# BMS.net
KiCad netlist of a schematic drawn in EAGLE
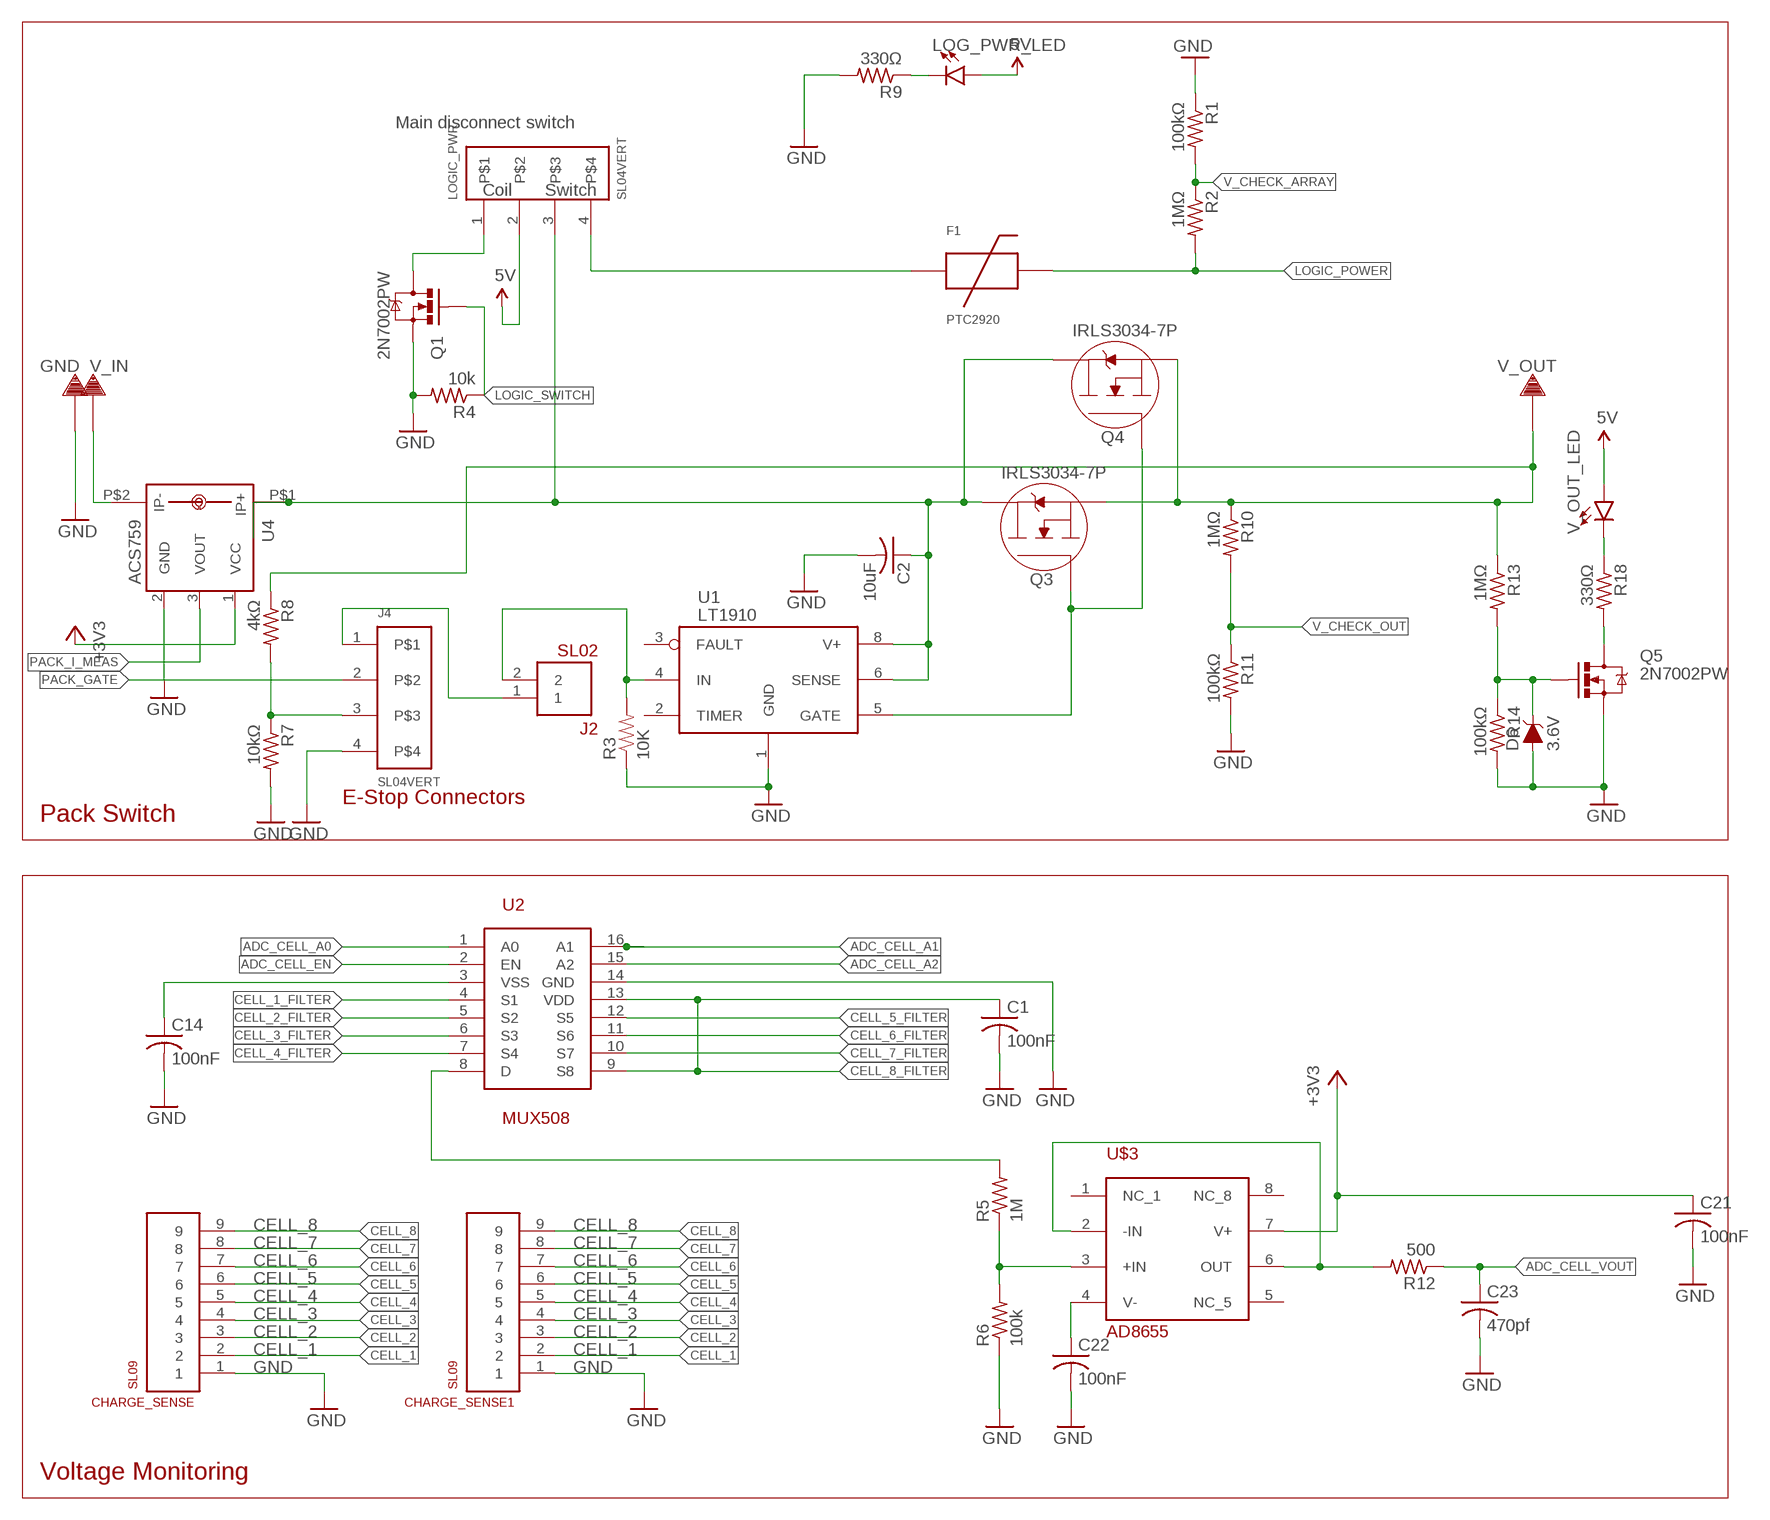
[diagram p0: schematic, sheet 1, part 1 of 2]
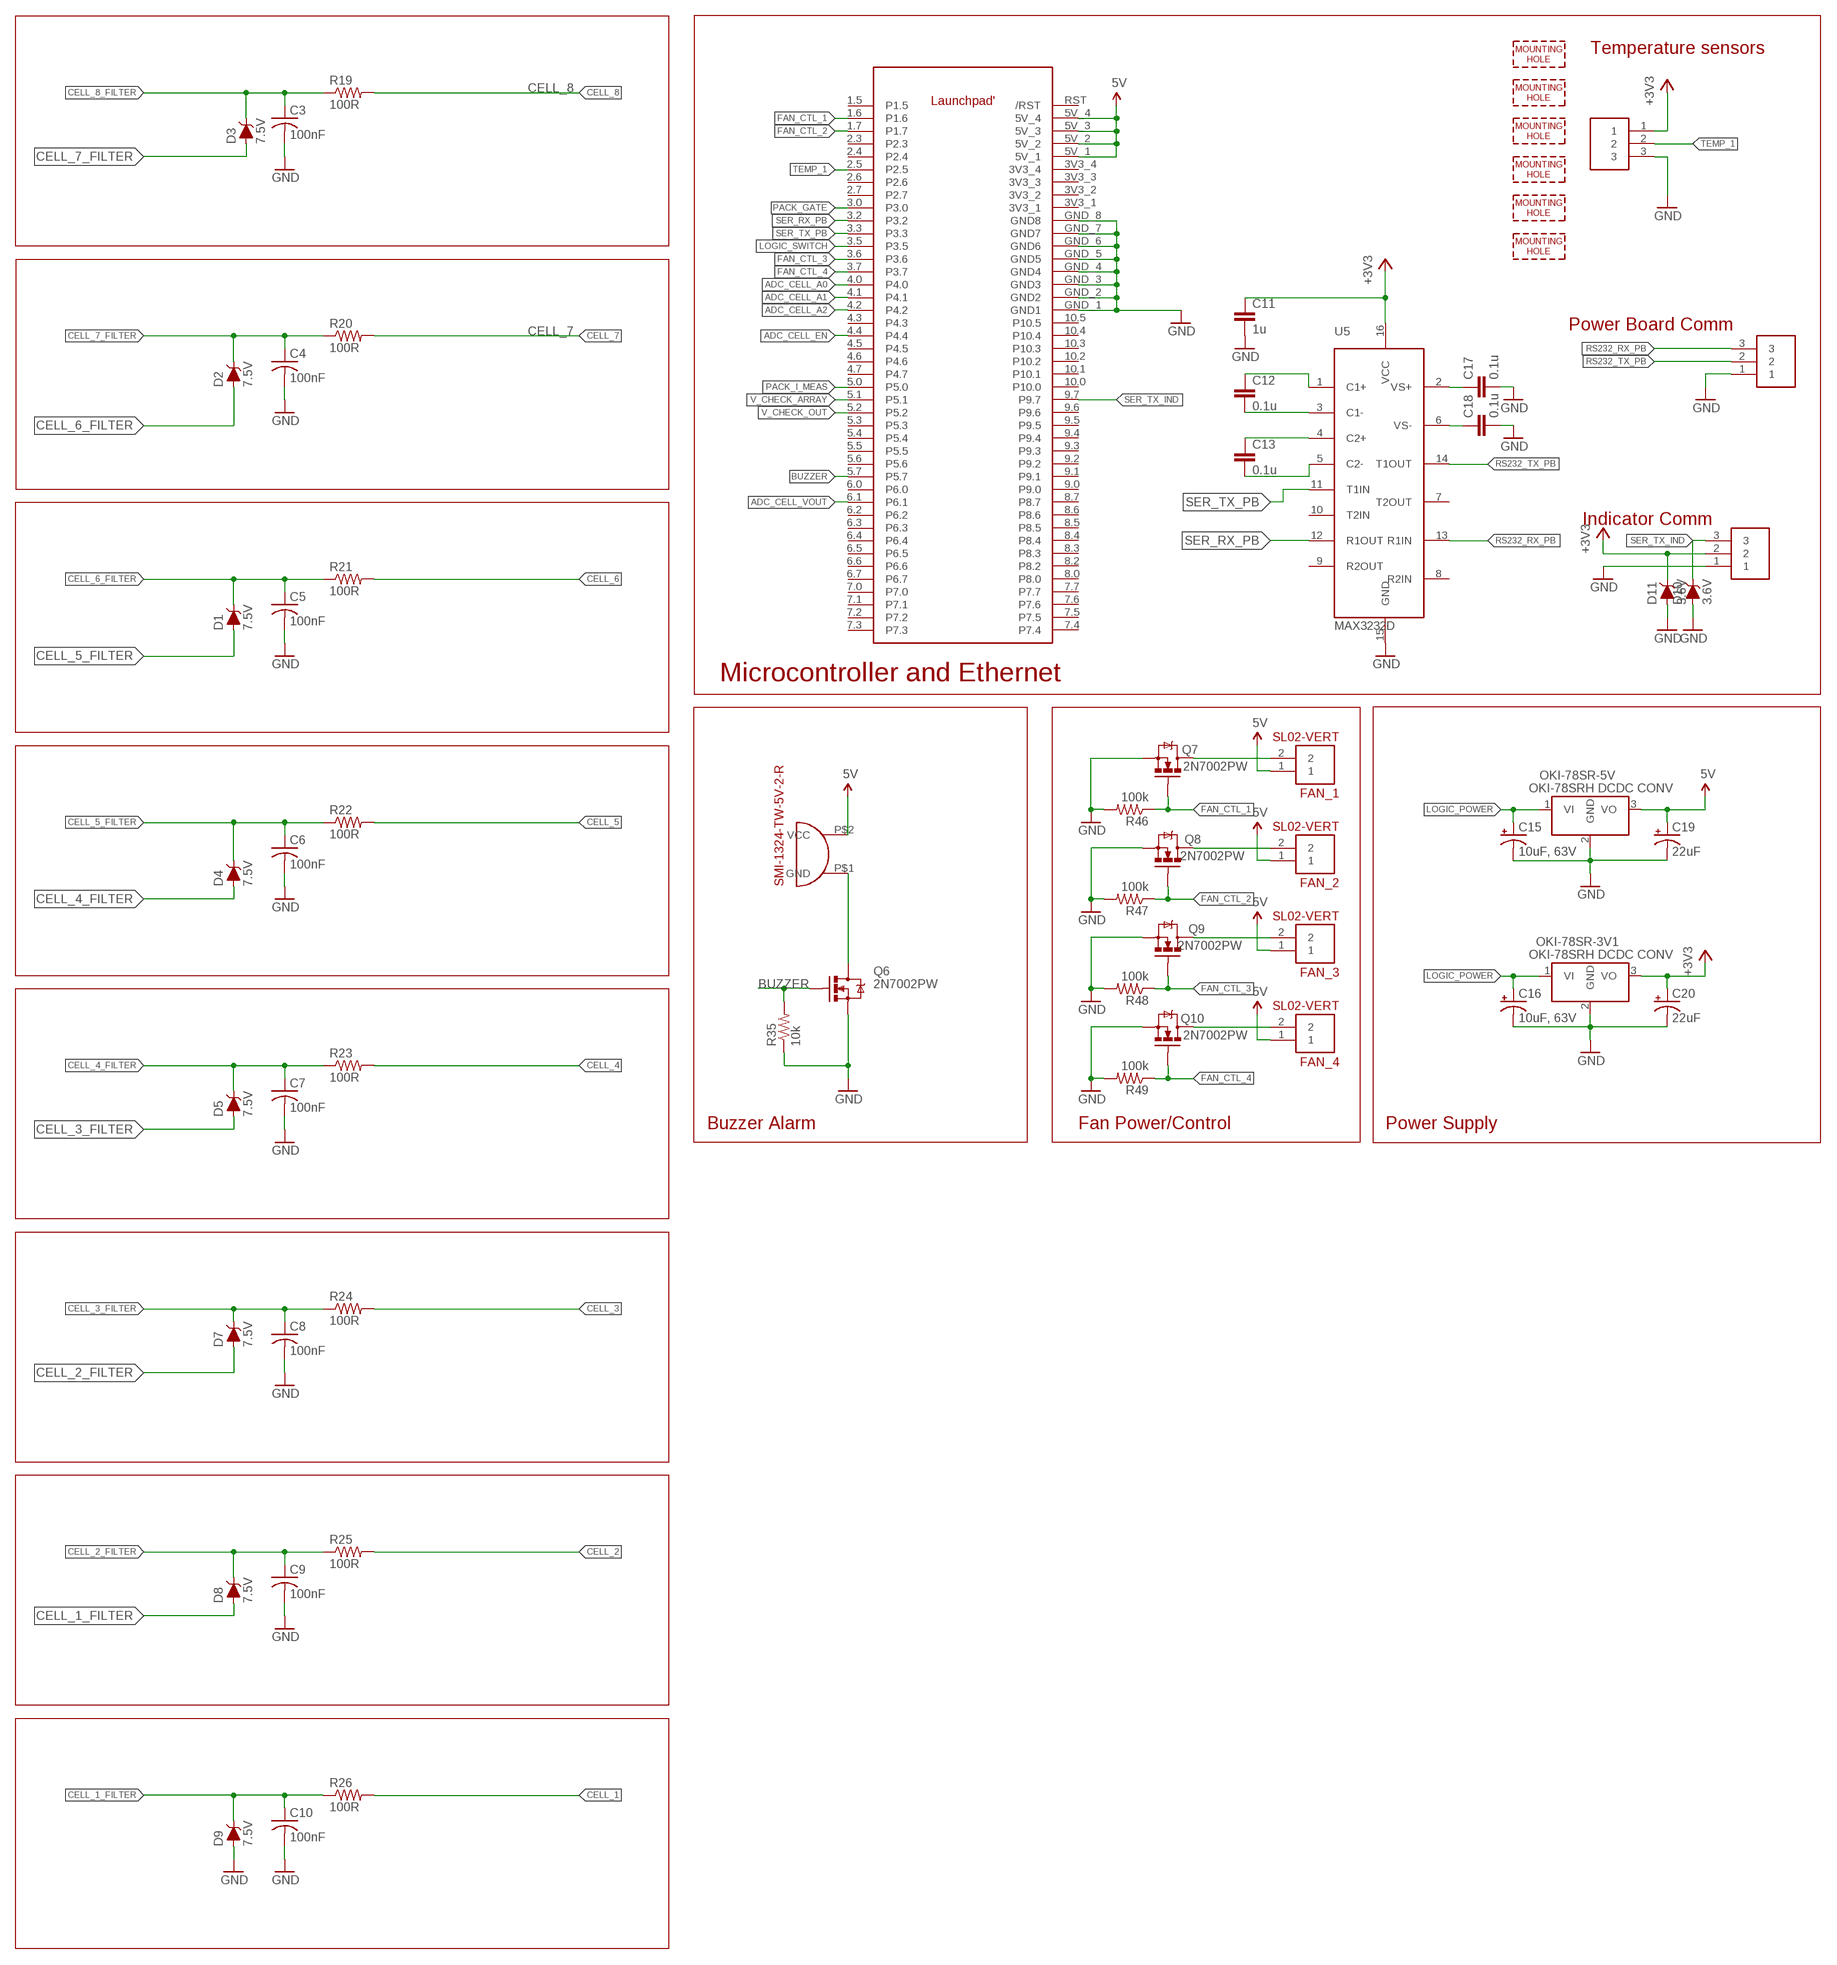
[diagram p1: schematic, sheet 1, part 2 of 2]

(export (version "E")
  (design (tool "Eeschema 10.0.6"))
  (components
    (comp (ref "C1")
      (value "100nF")
      (footprint "eagle-import:C0603")
      (libsource (lib "eagle-import") (part "C-USC0603"))
    )
    (comp (ref "C2")
      (value "10uF")
      (footprint "eagle-import:C0805")
      (libsource (lib "eagle-import") (part "C-USC0805"))
    )
    (comp (ref "C3")
      (value "100nF")
      (footprint "eagle-import:C0603")
      (libsource (lib "eagle-import") (part "C-USC0603"))
    )
    (comp (ref "C4")
      (value "100nF")
      (footprint "eagle-import:C0603")
      (libsource (lib "eagle-import") (part "C-USC0603"))
    )
    (comp (ref "C5")
      (value "100nF")
      (footprint "eagle-import:C0603")
      (libsource (lib "eagle-import") (part "C-USC0603"))
    )
    (comp (ref "C6")
      (value "100nF")
      (footprint "eagle-import:C0603")
      (libsource (lib "eagle-import") (part "C-USC0603"))
    )
    (comp (ref "C7")
      (value "100nF")
      (footprint "eagle-import:C0603")
      (libsource (lib "eagle-import") (part "C-USC0603"))
    )
    (comp (ref "C8")
      (value "100nF")
      (footprint "eagle-import:C0603")
      (libsource (lib "eagle-import") (part "C-USC0603"))
    )
    (comp (ref "C9")
      (value "100nF")
      (footprint "eagle-import:C0603")
      (libsource (lib "eagle-import") (part "C-USC0603"))
    )
    (comp (ref "C10")
      (value "100nF")
      (footprint "eagle-import:C0603")
      (libsource (lib "eagle-import") (part "C-USC0603"))
    )
    (comp (ref "C11")
      (value "1u")
      (footprint "eagle-import:0805")
      (libsource (lib "eagle-import") (part "CAP0805"))
    )
    (comp (ref "C12")
      (value "0.1u")
      (footprint "eagle-import:0805")
      (libsource (lib "eagle-import") (part "CAP0805"))
    )
    (comp (ref "C13")
      (value "0.1u")
      (footprint "eagle-import:0805")
      (libsource (lib "eagle-import") (part "CAP0805"))
    )
    (comp (ref "C14")
      (value "100nF")
      (footprint "eagle-import:C0603")
      (libsource (lib "eagle-import") (part "C-USC0603"))
    )
    (comp (ref "C15")
      (value "10uF, 63V")
      (footprint "eagle-import:PANASONIC_D")
      (libsource (lib "eagle-import") (part "CPOL-USD"))
    )
    (comp (ref "C16")
      (value "10uF, 63V")
      (footprint "eagle-import:PANASONIC_D")
      (libsource (lib "eagle-import") (part "CPOL-USD"))
    )
    (comp (ref "C17")
      (value "0.1u")
      (footprint "eagle-import:0805")
      (libsource (lib "eagle-import") (part "CAP0805"))
    )
    (comp (ref "C18")
      (value "0.1u")
      (footprint "eagle-import:0805")
      (libsource (lib "eagle-import") (part "CAP0805"))
    )
    (comp (ref "C19")
      (value "22uF")
      (footprint "eagle-import:PANASONIC_D")
      (libsource (lib "eagle-import") (part "CPOL-USD"))
    )
    (comp (ref "C20")
      (value "22uF")
      (footprint "eagle-import:PANASONIC_D")
      (libsource (lib "eagle-import") (part "CPOL-USD"))
    )
    (comp (ref "C21")
      (value "100nF")
      (footprint "eagle-import:C0603")
      (libsource (lib "eagle-import") (part "C-USC0603"))
    )
    (comp (ref "C22")
      (value "100nF")
      (footprint "eagle-import:C0603")
      (libsource (lib "eagle-import") (part "C-USC0603"))
    )
    (comp (ref "C23")
      (value "470pf")
      (footprint "eagle-import:C0603")
      (libsource (lib "eagle-import") (part "C-USC0603"))
    )
    (comp (ref "CHARGE_SENSE")
      (value "SL09")
      (footprint "eagle-import:MOLEX-70543-0008")
      (libsource (lib "eagle-import") (part "SL09"))
    )
    (comp (ref "CHARGE_SENSE1")
      (value "SL09")
      (footprint "eagle-import:MOLEX-70543-0008")
      (libsource (lib "eagle-import") (part "SL09"))
    )
    (comp (ref "D1")
      (value "7.5V")
      (footprint "eagle-import:SOD-323")
      (libsource (lib "eagle-import") (part "DIODE-ZENER-BZT52C3V6S"))
    )
    (comp (ref "D2")
      (value "7.5V")
      (footprint "eagle-import:SOD-323")
      (libsource (lib "eagle-import") (part "DIODE-ZENER-BZT52C3V6S"))
    )
    (comp (ref "D3")
      (value "7.5V")
      (footprint "eagle-import:SOD-323")
      (libsource (lib "eagle-import") (part "DIODE-ZENER-BZT52C3V6S"))
    )
    (comp (ref "D4")
      (value "7.5V")
      (footprint "eagle-import:SOD-323")
      (libsource (lib "eagle-import") (part "DIODE-ZENER-BZT52C3V6S"))
    )
    (comp (ref "D5")
      (value "7.5V")
      (footprint "eagle-import:SOD-323")
      (libsource (lib "eagle-import") (part "DIODE-ZENER-BZT52C3V6S"))
    )
    (comp (ref "D6")
      (value "3.6V")
      (footprint "eagle-import:SOD-323")
      (libsource (lib "eagle-import") (part "DIODE-ZENER-BZT52C3V6S"))
    )
    (comp (ref "D7")
      (value "7.5V")
      (footprint "eagle-import:SOD-323")
      (libsource (lib "eagle-import") (part "DIODE-ZENER-BZT52C3V6S"))
    )
    (comp (ref "D8")
      (value "7.5V")
      (footprint "eagle-import:SOD-323")
      (libsource (lib "eagle-import") (part "DIODE-ZENER-BZT52C3V6S"))
    )
    (comp (ref "D9")
      (value "7.5V")
      (footprint "eagle-import:SOD-323")
      (libsource (lib "eagle-import") (part "DIODE-ZENER-BZT52C3V6S"))
    )
    (comp (ref "D10")
      (value "3.6V")
      (footprint "eagle-import:SOD-323")
      (libsource (lib "eagle-import") (part "DIODE-ZENER-BZT52C3V6S"))
    )
    (comp (ref "D11")
      (value "3.6V")
      (footprint "eagle-import:SOD-323")
      (libsource (lib "eagle-import") (part "DIODE-ZENER-BZT52C3V6S"))
    )
    (comp (ref "F1")
      (value "PTC2920")
      (footprint "eagle-import:2920")
      (libsource (lib "eagle-import") (part "PTC2920"))
    )
    (comp (ref "FAN_1")
      (value "SL02-VERT")
      (footprint "eagle-import:MOLEX-70543-0001")
      (libsource (lib "eagle-import") (part "SL02-VERT"))
    )
    (comp (ref "FAN_2")
      (value "SL02-VERT")
      (footprint "eagle-import:MOLEX-70543-0001")
      (libsource (lib "eagle-import") (part "SL02-VERT"))
    )
    (comp (ref "FAN_3")
      (value "SL02-VERT")
      (footprint "eagle-import:MOLEX-70543-0001")
      (libsource (lib "eagle-import") (part "SL02-VERT"))
    )
    (comp (ref "FAN_4")
      (value "SL02-VERT")
      (footprint "eagle-import:MOLEX-70543-0001")
      (libsource (lib "eagle-import") (part "SL02-VERT"))
    )
    (comp (ref "GND")
      (value "TERMINAL_HOLE")
      (footprint "eagle-import:LARGE_TERMINAL_HOLE")
      (libsource (lib "eagle-import") (part "TERMINAL_HOLE"))
    )
    (comp (ref "H1")
      (value "MOUNTING_HOLE#4")
      (footprint "eagle-import:#4_SCREW")
      (libsource (lib "eagle-import") (part "MOUNTING_HOLE#4"))
    )
    (comp (ref "H2")
      (value "MOUNTING_HOLE#4")
      (footprint "eagle-import:#4_SCREW")
      (libsource (lib "eagle-import") (part "MOUNTING_HOLE#4"))
    )
    (comp (ref "H3")
      (value "MOUNTING_HOLE#4")
      (footprint "eagle-import:#4_SCREW")
      (libsource (lib "eagle-import") (part "MOUNTING_HOLE#4"))
    )
    (comp (ref "H4")
      (value "MOUNTING_HOLE#4")
      (footprint "eagle-import:#4_SCREW")
      (libsource (lib "eagle-import") (part "MOUNTING_HOLE#4"))
    )
    (comp (ref "H5")
      (value "MOUNTING_HOLE#4")
      (footprint "eagle-import:#4_SCREW")
      (libsource (lib "eagle-import") (part "MOUNTING_HOLE#4"))
    )
    (comp (ref "H6")
      (value "MOUNTING_HOLE#4")
      (footprint "eagle-import:#4_SCREW")
      (libsource (lib "eagle-import") (part "MOUNTING_HOLE#4"))
    )
    (comp (ref "IC2")
      (value "SMI-1324-TW-5V-2-R")
      (footprint "eagle-import:SMI-1324-TW-5V-2-R")
      (libsource (lib "eagle-import") (part "SMI-1324-TW-5V-2-R"))
    )
    (comp (ref "J1")
      (value "SL03")
      (footprint "eagle-import:MOLEX-70543-0002")
      (libsource (lib "eagle-import") (part "SL03"))
    )
    (comp (ref "J2")
      (value "SL02")
      (footprint "eagle-import:MOLEX-70543-0001")
      (libsource (lib "eagle-import") (part "SL02"))
    )
    (comp (ref "J4")
      (value "SL04VERT")
      (footprint "eagle-import:MOLEX-70543-0003")
      (libsource (lib "eagle-import") (part "SL04VERT"))
    )
    (comp (ref "LOGIC_PWR")
      (value "SL04VERT")
      (footprint "eagle-import:MOLEX-70543-0003")
      (libsource (lib "eagle-import") (part "SL04VERT"))
    )
    (comp (ref "LOG_PWR_LED")
      (value "LED1206")
      (footprint "eagle-import:LED-1206")
      (libsource (lib "eagle-import") (part "LED1206"))
    )
    (comp (ref "OKI-78SR-3V1")
      (value "Q_OKI-78SR12")
      (footprint "eagle-import:OKI-78SRH")
      (libsource (lib "eagle-import") (part "Q_OKI-78SR"))
    )
    (comp (ref "OKI-78SR-5V")
      (value "Q_OKI-78SR5")
      (footprint "eagle-import:OKI-78SRH")
      (libsource (lib "eagle-import") (part "Q_OKI-78SR"))
    )
    (comp (ref "Q1")
      (value "2N7002PW")
      (footprint "eagle-import:SOT323")
      (libsource (lib "eagle-import") (part "MOSFET-NCHANNEL2N7002PW"))
    )
    (comp (ref "Q3")
      (value "IRLS3034-7P")
      (footprint "eagle-import:D2PAK-7")
      (libsource (lib "eagle-import") (part "IRLS3034-7P"))
    )
    (comp (ref "Q4")
      (value "IRLS3034-7P")
      (footprint "eagle-import:D2PAK-7")
      (libsource (lib "eagle-import") (part "IRLS3034-7P"))
    )
    (comp (ref "Q5")
      (value "2N7002PW")
      (footprint "eagle-import:SOT323")
      (libsource (lib "eagle-import") (part "MOSFET-NCHANNEL2N7002PW"))
    )
    (comp (ref "Q6")
      (value "2N7002PW")
      (footprint "eagle-import:SOT323")
      (libsource (lib "eagle-import") (part "MOSFET-NCHANNEL2N7002PW"))
    )
    (comp (ref "Q7")
      (value "2N7002PW")
      (footprint "eagle-import:SOT323")
      (libsource (lib "eagle-import") (part "MOSFET-NCHANNEL2N7002PW"))
    )
    (comp (ref "Q8")
      (value "2N7002PW")
      (footprint "eagle-import:SOT323")
      (libsource (lib "eagle-import") (part "MOSFET-NCHANNEL2N7002PW"))
    )
    (comp (ref "Q9")
      (value "2N7002PW")
      (footprint "eagle-import:SOT323")
      (libsource (lib "eagle-import") (part "MOSFET-NCHANNEL2N7002PW"))
    )
    (comp (ref "Q10")
      (value "2N7002PW")
      (footprint "eagle-import:SOT323")
      (libsource (lib "eagle-import") (part "MOSFET-NCHANNEL2N7002PW"))
    )
    (comp (ref "R1")
      (value "100kΩ")
      (footprint "eagle-import:R0805")
      (libsource (lib "eagle-import") (part "R-US_R0805"))
    )
    (comp (ref "R2")
      (value "1MΩ")
      (footprint "eagle-import:R0805")
      (libsource (lib "eagle-import") (part "R-US_R0805"))
    )
    (comp (ref "R3")
      (value "10K")
      (footprint "eagle-import:0603-RES")
      (libsource (lib "eagle-import") (part "10KOHM-1/10W-1%(0603)0603"))
    )
    (comp (ref "R4")
      (value "10k")
      (footprint "eagle-import:R0805")
      (libsource (lib "eagle-import") (part "R-US_R0805"))
    )
    (comp (ref "R5")
      (value "1M")
      (footprint "eagle-import:M1206")
      (libsource (lib "eagle-import") (part "R-US_M1206"))
    )
    (comp (ref "R6")
      (value "100k")
      (footprint "eagle-import:M1206")
      (libsource (lib "eagle-import") (part "R-US_M1206"))
    )
    (comp (ref "R7")
      (value "10kΩ")
      (footprint "eagle-import:R0805")
      (libsource (lib "eagle-import") (part "R-US_R0805"))
    )
    (comp (ref "R8")
      (value "4kΩ")
      (footprint "eagle-import:R0805")
      (libsource (lib "eagle-import") (part "R-US_R0805"))
    )
    (comp (ref "R9")
      (value "330Ω")
      (footprint "eagle-import:R0805")
      (libsource (lib "eagle-import") (part "R-US_R0805"))
    )
    (comp (ref "R10")
      (value "1MΩ")
      (footprint "eagle-import:R0805")
      (libsource (lib "eagle-import") (part "R-US_R0805"))
    )
    (comp (ref "R11")
      (value "100kΩ")
      (footprint "eagle-import:R0805")
      (libsource (lib "eagle-import") (part "R-US_R0805"))
    )
    (comp (ref "R12")
      (value "500")
      (footprint "eagle-import:M1206")
      (libsource (lib "eagle-import") (part "R-US_M1206"))
    )
    (comp (ref "R13")
      (value "1MΩ")
      (footprint "eagle-import:R0805")
      (libsource (lib "eagle-import") (part "R-US_R0805"))
    )
    (comp (ref "R14")
      (value "100kΩ")
      (footprint "eagle-import:R0805")
      (libsource (lib "eagle-import") (part "R-US_R0805"))
    )
    (comp (ref "R18")
      (value "330Ω")
      (footprint "eagle-import:R0805")
      (libsource (lib "eagle-import") (part "R-US_R0805"))
    )
    (comp (ref "R19")
      (value "100R")
      (footprint "eagle-import:R0603")
      (libsource (lib "eagle-import") (part "R-US_R0603"))
    )
    (comp (ref "R20")
      (value "100R")
      (footprint "eagle-import:R0603")
      (libsource (lib "eagle-import") (part "R-US_R0603"))
    )
    (comp (ref "R21")
      (value "100R")
      (footprint "eagle-import:R0603")
      (libsource (lib "eagle-import") (part "R-US_R0603"))
    )
    (comp (ref "R22")
      (value "100R")
      (footprint "eagle-import:R0603")
      (libsource (lib "eagle-import") (part "R-US_R0603"))
    )
    (comp (ref "R23")
      (value "100R")
      (footprint "eagle-import:R0603")
      (libsource (lib "eagle-import") (part "R-US_R0603"))
    )
    (comp (ref "R24")
      (value "100R")
      (footprint "eagle-import:R0603")
      (libsource (lib "eagle-import") (part "R-US_R0603"))
    )
    (comp (ref "R25")
      (value "100R")
      (footprint "eagle-import:R0603")
      (libsource (lib "eagle-import") (part "R-US_R0603"))
    )
    (comp (ref "R26")
      (value "100R")
      (footprint "eagle-import:R0603")
      (libsource (lib "eagle-import") (part "R-US_R0603"))
    )
    (comp (ref "R35")
      (value "10k")
      (footprint "eagle-import:R0805")
      (libsource (lib "eagle-import") (part "R-US_R0805"))
    )
    (comp (ref "R46")
      (value "100k")
      (footprint "eagle-import:R0805")
      (libsource (lib "eagle-import") (part "R-US_R0805"))
    )
    (comp (ref "R47")
      (value "100k")
      (footprint "eagle-import:R0805")
      (libsource (lib "eagle-import") (part "R-US_R0805"))
    )
    (comp (ref "R48")
      (value "100k")
      (footprint "eagle-import:R0805")
      (libsource (lib "eagle-import") (part "R-US_R0805"))
    )
    (comp (ref "R49")
      (value "100k")
      (footprint "eagle-import:R0805")
      (libsource (lib "eagle-import") (part "R-US_R0805"))
    )
    (comp (ref "RS232_PB")
      (value "SL03")
      (footprint "eagle-import:MOLEX-70543-0002")
      (libsource (lib "eagle-import") (part "SL03"))
    )
    (comp (ref "TEMP_1")
      (value "SL03")
      (footprint "eagle-import:MOLEX-70543-0002")
      (libsource (lib "eagle-import") (part "SL03"))
    )
    (comp (ref "U$3")
      (value "AD8655")
      (footprint "eagle-import:SOIC8")
      (libsource (lib "eagle-import") (part "AD8655"))
    )
    (comp (ref "U1")
      (value "LT1910")
      (footprint "eagle-import:SO8")
      (libsource (lib "eagle-import") (part "LT1910"))
    )
    (comp (ref "U2")
      (value "MUX508")
      (footprint "eagle-import:SOIC16")
      (libsource (lib "eagle-import") (part "MUX508"))
    )
    (comp (ref "U3")
      (value "MSP430R401R")
      (footprint "eagle-import:MSP432R401R-LAUNCHPAD")
      (libsource (lib "eagle-import") (part "MSP430R401R"))
    )
    (comp (ref "U4")
      (value "ACS759")
      (footprint "eagle-import:ACS-PFF-LEADFORM")
      (libsource (lib "eagle-import") (part "ACS759"))
    )
    (comp (ref "U5")
      (value "MAX3232D")
      (footprint "eagle-import:SOIC16")
      (libsource (lib "eagle-import") (part "MAX232D3"))
    )
    (comp (ref "V_IN")
      (value "TERMINAL_HOLE")
      (footprint "eagle-import:LARGE_TERMINAL_HOLE")
      (libsource (lib "eagle-import") (part "TERMINAL_HOLE"))
    )
    (comp (ref "V_OUT")
      (value "TERMINAL_HOLE")
      (footprint "eagle-import:LARGE_TERMINAL_HOLE")
      (libsource (lib "eagle-import") (part "TERMINAL_HOLE"))
    )
    (comp (ref "V_OUT_LED")
      (value "LED1206")
      (footprint "eagle-import:LED-1206")
      (libsource (lib "eagle-import") (part "LED1206"))
    )
  )
  (nets
    (net (code "1") (name "+3V3") (class "Default")
      (node (ref "C11") (pin "1") (pinfunction "1_1") (pintype "passive"))
      (node (ref "C20") (pin "+") (pinfunction "+_+") (pintype "passive"))
      (node (ref "C21") (pin "1") (pinfunction "1_1") (pintype "passive"))
      (node (ref "D11") (pin "C") (pinfunction "C_C") (pintype "passive"))
      (node (ref "J1") (pin "2") (pinfunction "2_2") (pintype "bidirectional"))
      (node (ref "OKI-78SR-3V1") (pin "3") (pinfunction "VO_3") (pintype "bidirectional"))
      (node (ref "TEMP_1") (pin "1") (pinfunction "1_1") (pintype "bidirectional"))
      (node (ref "U$3") (pin "7") (pinfunction "V+_7") (pintype "bidirectional"))
      (node (ref "U4") (pin "1") (pinfunction "VCC_1") (pintype "power_in"))
      (node (ref "U5") (pin "16") (pinfunction "VCC_16") (pintype "bidirectional"))
    )
    (net (code "2") (name "5V") (class "Default")
      (node (ref "C19") (pin "+") (pinfunction "+_+") (pintype "passive"))
      (node (ref "FAN_1") (pin "1") (pinfunction "1_1") (pintype "bidirectional"))
      (node (ref "FAN_2") (pin "1") (pinfunction "1_1") (pintype "bidirectional"))
      (node (ref "FAN_3") (pin "1") (pinfunction "1_1") (pintype "bidirectional"))
      (node (ref "FAN_4") (pin "1") (pinfunction "1_1") (pintype "bidirectional"))
      (node (ref "IC2") (pin "P$2") (pinfunction "VCC_P$2") (pintype "bidirectional"))
      (node (ref "LOGIC_PWR") (pin "2") (pinfunction "P$2_2") (pintype "bidirectional"))
      (node (ref "LOG_PWR_LED") (pin "A") (pinfunction "A_A") (pintype "passive"))
      (node (ref "OKI-78SR-5V") (pin "3") (pinfunction "VO_3") (pintype "bidirectional"))
      (node (ref "U3") (pin "5V_1") (pinfunction "5V_1_5V_1") (pintype "bidirectional"))
      (node (ref "U3") (pin "5V_2") (pinfunction "5V_2_5V_2") (pintype "bidirectional"))
      (node (ref "U3") (pin "5V_3") (pinfunction "5V_3_5V_3") (pintype "bidirectional"))
      (node (ref "U3") (pin "5V_4") (pinfunction "5V_4_5V_4") (pintype "bidirectional"))
      (node (ref "V_OUT_LED") (pin "A") (pinfunction "A_A") (pintype "passive"))
    )
    (net (code "3") (name "ADC_CELL_A0") (class "Default")
      (node (ref "U2") (pin "1") (pinfunction "A0_1") (pintype "bidirectional"))
      (node (ref "U3") (pin "4.0") (pinfunction "P4.0_4.0") (pintype "bidirectional"))
    )
    (net (code "4") (name "ADC_CELL_A1") (class "Default")
      (node (ref "U2") (pin "16") (pinfunction "A1_16") (pintype "bidirectional"))
      (node (ref "U3") (pin "4.1") (pinfunction "P4.1_4.1") (pintype "bidirectional"))
    )
    (net (code "5") (name "ADC_CELL_A2") (class "Default")
      (node (ref "U2") (pin "15") (pinfunction "A2_15") (pintype "bidirectional"))
      (node (ref "U3") (pin "4.2") (pinfunction "P4.2_4.2") (pintype "bidirectional"))
    )
    (net (code "6") (name "ADC_CELL_EN") (class "Default")
      (node (ref "U2") (pin "2") (pinfunction "EN_2") (pintype "bidirectional"))
      (node (ref "U3") (pin "4.4") (pinfunction "P4.4_4.4") (pintype "bidirectional"))
    )
    (net (code "7") (name "ADC_CELL_VOUT") (class "Default")
      (node (ref "C23") (pin "1") (pinfunction "1_1") (pintype "passive"))
      (node (ref "R12") (pin "1") (pinfunction "1_1") (pintype "passive"))
      (node (ref "U3") (pin "6.1") (pinfunction "P6.1_6.1") (pintype "bidirectional"))
    )
    (net (code "8") (name "BUZZER") (class "Default")
      (node (ref "Q6") (pin "1") (pinfunction "G_1") (pintype "passive"))
      (node (ref "R35") (pin "2") (pinfunction "2_2") (pintype "passive"))
      (node (ref "U3") (pin "5.7") (pinfunction "P5.7_5.7") (pintype "bidirectional"))
    )
    (net (code "9") (name "CELL_1") (class "Default")
      (node (ref "CHARGE_SENSE") (pin "2") (pinfunction "2_2") (pintype "bidirectional"))
      (node (ref "CHARGE_SENSE1") (pin "2") (pinfunction "2_2") (pintype "bidirectional"))
      (node (ref "R26") (pin "2") (pinfunction "2_2") (pintype "passive"))
    )
    (net (code "10") (name "CELL_1_FILTER") (class "Default")
      (node (ref "C10") (pin "1") (pinfunction "1_1") (pintype "passive"))
      (node (ref "D8") (pin "A") (pinfunction "A_A") (pintype "passive"))
      (node (ref "D9") (pin "C") (pinfunction "C_C") (pintype "passive"))
      (node (ref "R26") (pin "1") (pinfunction "1_1") (pintype "passive"))
      (node (ref "U2") (pin "4") (pinfunction "S1_4") (pintype "bidirectional"))
    )
    (net (code "11") (name "CELL_2") (class "Default")
      (node (ref "CHARGE_SENSE") (pin "3") (pinfunction "3_3") (pintype "bidirectional"))
      (node (ref "CHARGE_SENSE1") (pin "3") (pinfunction "3_3") (pintype "bidirectional"))
      (node (ref "R25") (pin "2") (pinfunction "2_2") (pintype "passive"))
    )
    (net (code "12") (name "CELL_2_FILTER") (class "Default")
      (node (ref "C9") (pin "1") (pinfunction "1_1") (pintype "passive"))
      (node (ref "D7") (pin "A") (pinfunction "A_A") (pintype "passive"))
      (node (ref "D8") (pin "C") (pinfunction "C_C") (pintype "passive"))
      (node (ref "R25") (pin "1") (pinfunction "1_1") (pintype "passive"))
      (node (ref "U2") (pin "5") (pinfunction "S2_5") (pintype "bidirectional"))
    )
    (net (code "13") (name "CELL_3") (class "Default")
      (node (ref "CHARGE_SENSE") (pin "4") (pinfunction "4_4") (pintype "bidirectional"))
      (node (ref "CHARGE_SENSE1") (pin "4") (pinfunction "4_4") (pintype "bidirectional"))
      (node (ref "R24") (pin "2") (pinfunction "2_2") (pintype "passive"))
    )
    (net (code "14") (name "CELL_3_FILTER") (class "Default")
      (node (ref "C8") (pin "1") (pinfunction "1_1") (pintype "passive"))
      (node (ref "D5") (pin "A") (pinfunction "A_A") (pintype "passive"))
      (node (ref "D7") (pin "C") (pinfunction "C_C") (pintype "passive"))
      (node (ref "R24") (pin "1") (pinfunction "1_1") (pintype "passive"))
      (node (ref "U2") (pin "6") (pinfunction "S3_6") (pintype "bidirectional"))
    )
    (net (code "15") (name "CELL_4") (class "Default")
      (node (ref "CHARGE_SENSE") (pin "5") (pinfunction "5_5") (pintype "bidirectional"))
      (node (ref "CHARGE_SENSE1") (pin "5") (pinfunction "5_5") (pintype "bidirectional"))
      (node (ref "R23") (pin "2") (pinfunction "2_2") (pintype "passive"))
    )
    (net (code "16") (name "CELL_4_FILTER") (class "Default")
      (node (ref "C7") (pin "1") (pinfunction "1_1") (pintype "passive"))
      (node (ref "D4") (pin "A") (pinfunction "A_A") (pintype "passive"))
      (node (ref "D5") (pin "C") (pinfunction "C_C") (pintype "passive"))
      (node (ref "R23") (pin "1") (pinfunction "1_1") (pintype "passive"))
      (node (ref "U2") (pin "7") (pinfunction "S4_7") (pintype "bidirectional"))
    )
    (net (code "17") (name "CELL_5") (class "Default")
      (node (ref "CHARGE_SENSE") (pin "6") (pinfunction "6_6") (pintype "bidirectional"))
      (node (ref "CHARGE_SENSE1") (pin "6") (pinfunction "6_6") (pintype "bidirectional"))
      (node (ref "R22") (pin "2") (pinfunction "2_2") (pintype "passive"))
    )
    (net (code "18") (name "CELL_5_FILTER") (class "Default")
      (node (ref "C6") (pin "1") (pinfunction "1_1") (pintype "passive"))
      (node (ref "D1") (pin "A") (pinfunction "A_A") (pintype "passive"))
      (node (ref "D4") (pin "C") (pinfunction "C_C") (pintype "passive"))
      (node (ref "R22") (pin "1") (pinfunction "1_1") (pintype "passive"))
      (node (ref "U2") (pin "12") (pinfunction "S5_12") (pintype "bidirectional"))
    )
    (net (code "19") (name "CELL_6") (class "Default")
      (node (ref "CHARGE_SENSE") (pin "7") (pinfunction "7_7") (pintype "bidirectional"))
      (node (ref "CHARGE_SENSE1") (pin "7") (pinfunction "7_7") (pintype "bidirectional"))
      (node (ref "R21") (pin "2") (pinfunction "2_2") (pintype "passive"))
    )
    (net (code "20") (name "CELL_6_FILTER") (class "Default")
      (node (ref "C5") (pin "1") (pinfunction "1_1") (pintype "passive"))
      (node (ref "D1") (pin "C") (pinfunction "C_C") (pintype "passive"))
      (node (ref "D2") (pin "A") (pinfunction "A_A") (pintype "passive"))
      (node (ref "R21") (pin "1") (pinfunction "1_1") (pintype "passive"))
      (node (ref "U2") (pin "11") (pinfunction "S6_11") (pintype "bidirectional"))
    )
    (net (code "21") (name "CELL_7") (class "Default")
      (node (ref "CHARGE_SENSE") (pin "8") (pinfunction "8_8") (pintype "bidirectional"))
      (node (ref "CHARGE_SENSE1") (pin "8") (pinfunction "8_8") (pintype "bidirectional"))
      (node (ref "R20") (pin "2") (pinfunction "2_2") (pintype "passive"))
    )
    (net (code "22") (name "CELL_7_FILTER") (class "Default")
      (node (ref "C4") (pin "1") (pinfunction "1_1") (pintype "passive"))
      (node (ref "D2") (pin "C") (pinfunction "C_C") (pintype "passive"))
      (node (ref "D3") (pin "A") (pinfunction "A_A") (pintype "passive"))
      (node (ref "R20") (pin "1") (pinfunction "1_1") (pintype "passive"))
      (node (ref "U2") (pin "10") (pinfunction "S7_10") (pintype "bidirectional"))
    )
    (net (code "23") (name "CELL_8") (class "Default")
      (node (ref "CHARGE_SENSE") (pin "9") (pinfunction "9_9") (pintype "bidirectional"))
      (node (ref "CHARGE_SENSE1") (pin "9") (pinfunction "9_9") (pintype "bidirectional"))
      (node (ref "R19") (pin "2") (pinfunction "2_2") (pintype "passive"))
    )
    (net (code "24") (name "CELL_8_FILTER") (class "Default")
      (node (ref "C1") (pin "1") (pinfunction "1_1") (pintype "passive"))
      (node (ref "C3") (pin "1") (pinfunction "1_1") (pintype "passive"))
      (node (ref "D3") (pin "C") (pinfunction "C_C") (pintype "passive"))
      (node (ref "R19") (pin "1") (pinfunction "1_1") (pintype "passive"))
      (node (ref "U2") (pin "13") (pinfunction "VDD_13") (pintype "bidirectional"))
      (node (ref "U2") (pin "9") (pinfunction "S8_9") (pintype "bidirectional"))
    )
    (net (code "25") (name "FAN_CTL_1") (class "Default")
      (node (ref "Q7") (pin "1") (pinfunction "G_1") (pintype "passive"))
      (node (ref "R46") (pin "1") (pinfunction "1_1") (pintype "passive"))
      (node (ref "U3") (pin "1.6") (pinfunction "P1.6_1.6") (pintype "bidirectional"))
    )
    (net (code "26") (name "FAN_CTL_2") (class "Default")
      (node (ref "Q8") (pin "1") (pinfunction "G_1") (pintype "passive"))
      (node (ref "R47") (pin "1") (pinfunction "1_1") (pintype "passive"))
      (node (ref "U3") (pin "1.7") (pinfunction "P1.7_1.7") (pintype "bidirectional"))
    )
    (net (code "27") (name "FAN_CTL_3") (class "Default")
      (node (ref "Q9") (pin "1") (pinfunction "G_1") (pintype "passive"))
      (node (ref "R48") (pin "1") (pinfunction "1_1") (pintype "passive"))
      (node (ref "U3") (pin "3.6") (pinfunction "P3.6_3.6") (pintype "bidirectional"))
    )
    (net (code "28") (name "FAN_CTL_4") (class "Default")
      (node (ref "Q10") (pin "1") (pinfunction "G_1") (pintype "passive"))
      (node (ref "R49") (pin "1") (pinfunction "1_1") (pintype "passive"))
      (node (ref "U3") (pin "3.7") (pinfunction "P3.7_3.7") (pintype "bidirectional"))
    )
    (net (code "29") (name "GND") (class "Default")
      (node (ref "C1") (pin "2") (pinfunction "2_2") (pintype "passive"))
      (node (ref "C10") (pin "2") (pinfunction "2_2") (pintype "passive"))
      (node (ref "C11") (pin "2") (pinfunction "2_2") (pintype "passive"))
      (node (ref "C14") (pin "2") (pinfunction "2_2") (pintype "passive"))
      (node (ref "C15") (pin "-") (pinfunction "-_-") (pintype "passive"))
      (node (ref "C16") (pin "-") (pinfunction "-_-") (pintype "passive"))
      (node (ref "C17") (pin "2") (pinfunction "2_2") (pintype "passive"))
      (node (ref "C18") (pin "2") (pinfunction "2_2") (pintype "passive"))
      (node (ref "C19") (pin "-") (pinfunction "-_-") (pintype "passive"))
      (node (ref "C2") (pin "2") (pinfunction "2_2") (pintype "passive"))
      (node (ref "C20") (pin "-") (pinfunction "-_-") (pintype "passive"))
      (node (ref "C21") (pin "2") (pinfunction "2_2") (pintype "passive"))
      (node (ref "C22") (pin "2") (pinfunction "2_2") (pintype "passive"))
      (node (ref "C23") (pin "2") (pinfunction "2_2") (pintype "passive"))
      (node (ref "C3") (pin "2") (pinfunction "2_2") (pintype "passive"))
      (node (ref "C4") (pin "2") (pinfunction "2_2") (pintype "passive"))
      (node (ref "C5") (pin "2") (pinfunction "2_2") (pintype "passive"))
      (node (ref "C6") (pin "2") (pinfunction "2_2") (pintype "passive"))
      (node (ref "C7") (pin "2") (pinfunction "2_2") (pintype "passive"))
      (node (ref "C8") (pin "2") (pinfunction "2_2") (pintype "passive"))
      (node (ref "C9") (pin "2") (pinfunction "2_2") (pintype "passive"))
      (node (ref "CHARGE_SENSE") (pin "1") (pinfunction "1_1") (pintype "bidirectional"))
      (node (ref "CHARGE_SENSE1") (pin "1") (pinfunction "1_1") (pintype "bidirectional"))
      (node (ref "D10") (pin "A") (pinfunction "A_A") (pintype "passive"))
      (node (ref "D11") (pin "A") (pinfunction "A_A") (pintype "passive"))
      (node (ref "D6") (pin "A") (pinfunction "A_A") (pintype "passive"))
      (node (ref "D9") (pin "A") (pinfunction "A_A") (pintype "passive"))
      (node (ref "GND") (pin "P$1") (pinfunction "P$1_P$1") (pintype "bidirectional"))
      (node (ref "J1") (pin "1") (pinfunction "1_1") (pintype "bidirectional"))
      (node (ref "J4") (pin "4") (pinfunction "P$4_4") (pintype "bidirectional"))
      (node (ref "OKI-78SR-3V1") (pin "2") (pinfunction "GND_2") (pintype "bidirectional"))
      (node (ref "OKI-78SR-5V") (pin "2") (pinfunction "GND_2") (pintype "bidirectional"))
      (node (ref "Q1") (pin "2") (pinfunction "S_2") (pintype "passive"))
      (node (ref "Q10") (pin "2") (pinfunction "S_2") (pintype "passive"))
      (node (ref "Q5") (pin "2") (pinfunction "S_2") (pintype "passive"))
      (node (ref "Q6") (pin "2") (pinfunction "S_2") (pintype "passive"))
      (node (ref "Q7") (pin "2") (pinfunction "S_2") (pintype "passive"))
      (node (ref "Q8") (pin "2") (pinfunction "S_2") (pintype "passive"))
      (node (ref "Q9") (pin "2") (pinfunction "S_2") (pintype "passive"))
      (node (ref "R1") (pin "1") (pinfunction "1_1") (pintype "passive"))
      (node (ref "R11") (pin "2") (pinfunction "2_2") (pintype "passive"))
      (node (ref "R14") (pin "2") (pinfunction "2_2") (pintype "passive"))
      (node (ref "R3") (pin "1") (pinfunction "1_1") (pintype "passive"))
      (node (ref "R35") (pin "1") (pinfunction "1_1") (pintype "passive"))
      (node (ref "R4") (pin "2") (pinfunction "2_2") (pintype "passive"))
      (node (ref "R46") (pin "2") (pinfunction "2_2") (pintype "passive"))
      (node (ref "R47") (pin "2") (pinfunction "2_2") (pintype "passive"))
      (node (ref "R48") (pin "2") (pinfunction "2_2") (pintype "passive"))
      (node (ref "R49") (pin "2") (pinfunction "2_2") (pintype "passive"))
      (node (ref "R6") (pin "1") (pinfunction "1_1") (pintype "passive"))
      (node (ref "R7") (pin "2") (pinfunction "2_2") (pintype "passive"))
      (node (ref "R9") (pin "2") (pinfunction "2_2") (pintype "passive"))
      (node (ref "RS232_PB") (pin "1") (pinfunction "1_1") (pintype "bidirectional"))
      (node (ref "TEMP_1") (pin "3") (pinfunction "3_3") (pintype "bidirectional"))
      (node (ref "U1") (pin "1") (pinfunction "GND_1") (pintype "bidirectional"))
      (node (ref "U2") (pin "14") (pinfunction "GND_14") (pintype "bidirectional"))
      (node (ref "U3") (pin "GND_1") (pinfunction "GND1_GND_1") (pintype "bidirectional"))
      (node (ref "U3") (pin "GND_2") (pinfunction "GND2_GND_2") (pintype "bidirectional"))
      (node (ref "U3") (pin "GND_3") (pinfunction "GND3_GND_3") (pintype "bidirectional"))
      (node (ref "U3") (pin "GND_4") (pinfunction "GND4_GND_4") (pintype "bidirectional"))
      (node (ref "U3") (pin "GND_5") (pinfunction "GND5_GND_5") (pintype "bidirectional"))
      (node (ref "U3") (pin "GND_6") (pinfunction "GND6_GND_6") (pintype "bidirectional"))
      (node (ref "U3") (pin "GND_7") (pinfunction "GND7_GND_7") (pintype "bidirectional"))
      (node (ref "U3") (pin "GND_8") (pinfunction "GND8_GND_8") (pintype "bidirectional"))
      (node (ref "U4") (pin "2") (pinfunction "GND_2") (pintype "power_in"))
      (node (ref "U5") (pin "15") (pinfunction "GND_15") (pintype "bidirectional"))
    )
    (net (code "30") (name "LOGIC_POWER") (class "Default")
      (node (ref "C15") (pin "+") (pinfunction "+_+") (pintype "passive"))
      (node (ref "C16") (pin "+") (pinfunction "+_+") (pintype "passive"))
      (node (ref "F1") (pin "P$2") (pinfunction "P$2_P$2") (pintype "bidirectional"))
      (node (ref "OKI-78SR-3V1") (pin "1") (pinfunction "VI_1") (pintype "bidirectional"))
      (node (ref "OKI-78SR-5V") (pin "1") (pinfunction "VI_1") (pintype "bidirectional"))
      (node (ref "R2") (pin "2") (pinfunction "2_2") (pintype "passive"))
    )
    (net (code "31") (name "LOGIC_SWITCH") (class "Default")
      (node (ref "Q1") (pin "1") (pinfunction "G_1") (pintype "passive"))
      (node (ref "R4") (pin "1") (pinfunction "1_1") (pintype "passive"))
      (node (ref "U3") (pin "3.5") (pinfunction "P3.5_3.5") (pintype "bidirectional"))
    )
    (net (code "32") (name "Net-(IC2-GND)") (class "Default")
      (node (ref "IC2") (pin "P$1") (pinfunction "GND_P$1") (pintype "bidirectional"))
      (node (ref "Q6") (pin "3") (pinfunction "D_3") (pintype "passive"))
    )
    (net (code "33") (name "Net-(J4-P$1)") (class "Default")
      (node (ref "J2") (pin "1") (pinfunction "1_1") (pintype "bidirectional"))
      (node (ref "J4") (pin "1") (pinfunction "P$1_1") (pintype "bidirectional"))
    )
    (net (code "34") (name "Net-(J4-P$3)") (class "Default")
      (node (ref "J4") (pin "3") (pinfunction "P$3_3") (pintype "bidirectional"))
      (node (ref "R7") (pin "1") (pinfunction "1_1") (pintype "passive"))
      (node (ref "R8") (pin "2") (pinfunction "2_2") (pintype "passive"))
    )
    (net (code "35") (name "Net-(LOGIC_PWR-P$1)") (class "Default")
      (node (ref "LOGIC_PWR") (pin "1") (pinfunction "P$1_1") (pintype "bidirectional"))
      (node (ref "Q1") (pin "3") (pinfunction "D_3") (pintype "passive"))
    )
    (net (code "36") (name "Net-(LOGIC_PWR-P$3)") (class "Default")
      (node (ref "C2") (pin "1") (pinfunction "1_1") (pintype "passive"))
      (node (ref "LOGIC_PWR") (pin "3") (pinfunction "P$3_3") (pintype "bidirectional"))
      (node (ref "Q3") (pin "PAD") (pinfunction "DRAIN_PAD") (pintype "bidirectional"))
      (node (ref "Q4") (pin "PAD") (pinfunction "DRAIN_PAD") (pintype "bidirectional"))
      (node (ref "U1") (pin "6") (pinfunction "SENSE_6") (pintype "bidirectional"))
      (node (ref "U1") (pin "8") (pinfunction "V+_8") (pintype "bidirectional"))
      (node (ref "U4") (pin "P$1") (pinfunction "IP+_P$1") (pintype "passive"))
    )
    (net (code "37") (name "Net-(LOGIC_PWR-P$4)") (class "Default")
      (node (ref "F1") (pin "P$1") (pinfunction "P$1_P$1") (pintype "bidirectional"))
      (node (ref "LOGIC_PWR") (pin "4") (pinfunction "P$4_4") (pintype "bidirectional"))
    )
    (net (code "38") (name "Net-(LOG_PWR_LED-PadC)") (class "Default")
      (node (ref "LOG_PWR_LED") (pin "C") (pinfunction "C_C") (pintype "passive"))
      (node (ref "R9") (pin "1") (pinfunction "1_1") (pintype "passive"))
    )
    (net (code "39") (name "Net-(Q3-GATE)") (class "Default")
      (node (ref "Q3") (pin "1") (pinfunction "GATE_1") (pintype "bidirectional"))
      (node (ref "Q4") (pin "1") (pinfunction "GATE_1") (pintype "bidirectional"))
      (node (ref "U1") (pin "5") (pinfunction "GATE_5") (pintype "bidirectional"))
    )
    (net (code "40") (name "Net-(Q3-SOURCE-Pad2)") (class "Default")
      (node (ref "Q3") (pin "2") (pinfunction "SOURCE_2") (pintype "bidirectional"))
      (node (ref "Q3") (pin "3") (pinfunction "SOURCE_3") (pintype "bidirectional"))
      (node (ref "Q3") (pin "4") (pinfunction "SOURCE_4") (pintype "bidirectional"))
      (node (ref "Q3") (pin "5") (pinfunction "SOURCE_5") (pintype "bidirectional"))
      (node (ref "Q3") (pin "6") (pinfunction "SOURCE_6") (pintype "bidirectional"))
      (node (ref "Q4") (pin "2") (pinfunction "SOURCE_2") (pintype "bidirectional"))
      (node (ref "Q4") (pin "3") (pinfunction "SOURCE_3") (pintype "bidirectional"))
      (node (ref "Q4") (pin "4") (pinfunction "SOURCE_4") (pintype "bidirectional"))
      (node (ref "Q4") (pin "5") (pinfunction "SOURCE_5") (pintype "bidirectional"))
      (node (ref "Q4") (pin "6") (pinfunction "SOURCE_6") (pintype "bidirectional"))
      (node (ref "R10") (pin "1") (pinfunction "1_1") (pintype "passive"))
      (node (ref "R13") (pin "1") (pinfunction "1_1") (pintype "passive"))
      (node (ref "R8") (pin "1") (pinfunction "1_1") (pintype "passive"))
      (node (ref "V_OUT") (pin "P$1") (pinfunction "P$1_P$1") (pintype "bidirectional"))
    )
    (net (code "41") (name "Net-(Q5-D)") (class "Default")
      (node (ref "Q5") (pin "3") (pinfunction "D_3") (pintype "passive"))
      (node (ref "R18") (pin "2") (pinfunction "2_2") (pintype "passive"))
    )
    (net (code "42") (name "Net-(Q5-G)") (class "Default")
      (node (ref "D6") (pin "C") (pinfunction "C_C") (pintype "passive"))
      (node (ref "Q5") (pin "1") (pinfunction "G_1") (pintype "passive"))
      (node (ref "R13") (pin "2") (pinfunction "2_2") (pintype "passive"))
      (node (ref "R14") (pin "1") (pinfunction "1_1") (pintype "passive"))
    )
    (net (code "43") (name "Net-(Q7-D)") (class "Default")
      (node (ref "FAN_1") (pin "2") (pinfunction "2_2") (pintype "bidirectional"))
      (node (ref "Q7") (pin "3") (pinfunction "D_3") (pintype "passive"))
    )
    (net (code "44") (name "Net-(Q8-D)") (class "Default")
      (node (ref "FAN_2") (pin "2") (pinfunction "2_2") (pintype "bidirectional"))
      (node (ref "Q8") (pin "3") (pinfunction "D_3") (pintype "passive"))
    )
    (net (code "45") (name "Net-(Q9-D)") (class "Default")
      (node (ref "FAN_3") (pin "2") (pinfunction "2_2") (pintype "bidirectional"))
      (node (ref "Q9") (pin "3") (pinfunction "D_3") (pintype "passive"))
    )
    (net (code "46") (name "Net-(Q10-D)") (class "Default")
      (node (ref "FAN_4") (pin "2") (pinfunction "2_2") (pintype "bidirectional"))
      (node (ref "Q10") (pin "3") (pinfunction "D_3") (pintype "passive"))
    )
    (net (code "47") (name "Net-(R18-Pad1)") (class "Default")
      (node (ref "R18") (pin "1") (pinfunction "1_1") (pintype "passive"))
      (node (ref "V_OUT_LED") (pin "C") (pinfunction "C_C") (pintype "passive"))
    )
    (net (code "48") (name "Net-(U$3-+IN)") (class "Default")
      (node (ref "R5") (pin "1") (pinfunction "1_1") (pintype "passive"))
      (node (ref "R6") (pin "2") (pinfunction "2_2") (pintype "passive"))
      (node (ref "U$3") (pin "3") (pinfunction "+IN_3") (pintype "bidirectional"))
    )
    (net (code "49") (name "Net-(U$3--IN)") (class "Default")
      (node (ref "R12") (pin "2") (pinfunction "2_2") (pintype "passive"))
      (node (ref "U$3") (pin "2") (pinfunction "-IN_2") (pintype "bidirectional"))
      (node (ref "U$3") (pin "6") (pinfunction "OUT_6") (pintype "bidirectional"))
    )
    (net (code "50") (name "Net-(U$3-V-)") (class "Default")
      (node (ref "C22") (pin "1") (pinfunction "1_1") (pintype "passive"))
      (node (ref "U$3") (pin "4") (pinfunction "V-_4") (pintype "bidirectional"))
    )
    (net (code "51") (name "Net-(U1-IN)") (class "Default")
      (node (ref "J2") (pin "2") (pinfunction "2_2") (pintype "bidirectional"))
      (node (ref "R3") (pin "2") (pinfunction "2_2") (pintype "passive"))
      (node (ref "U1") (pin "4") (pinfunction "IN_4") (pintype "bidirectional"))
    )
    (net (code "52") (name "Net-(U2-D)") (class "Default")
      (node (ref "R5") (pin "2") (pinfunction "2_2") (pintype "passive"))
      (node (ref "U2") (pin "8") (pinfunction "D_8") (pintype "bidirectional"))
    )
    (net (code "53") (name "Net-(U2-VSS)") (class "Default")
      (node (ref "C14") (pin "1") (pinfunction "1_1") (pintype "passive"))
      (node (ref "U2") (pin "3") (pinfunction "VSS_3") (pintype "bidirectional"))
    )
    (net (code "54") (name "Net-(U4-IP-)") (class "Default")
      (node (ref "U4") (pin "P$2") (pinfunction "IP-_P$2") (pintype "passive"))
      (node (ref "V_IN") (pin "P$1") (pinfunction "P$1_P$1") (pintype "bidirectional"))
    )
    (net (code "55") (name "Net-(U5-C1+)") (class "Default")
      (node (ref "C12") (pin "1") (pinfunction "1_1") (pintype "passive"))
      (node (ref "U5") (pin "1") (pinfunction "C1+_1") (pintype "bidirectional"))
    )
    (net (code "56") (name "Net-(U5-C1-)") (class "Default")
      (node (ref "C12") (pin "2") (pinfunction "2_2") (pintype "passive"))
      (node (ref "U5") (pin "3") (pinfunction "C1-_3") (pintype "bidirectional"))
    )
    (net (code "57") (name "Net-(U5-C2+)") (class "Default")
      (node (ref "C13") (pin "1") (pinfunction "1_1") (pintype "passive"))
      (node (ref "U5") (pin "4") (pinfunction "C2+_4") (pintype "bidirectional"))
    )
    (net (code "58") (name "Net-(U5-C2-)") (class "Default")
      (node (ref "C13") (pin "2") (pinfunction "2_2") (pintype "passive"))
      (node (ref "U5") (pin "5") (pinfunction "C2-_5") (pintype "bidirectional"))
    )
    (net (code "59") (name "Net-(U5-VS+)") (class "Default")
      (node (ref "C17") (pin "1") (pinfunction "1_1") (pintype "passive"))
      (node (ref "U5") (pin "2") (pinfunction "VS+_2") (pintype "bidirectional"))
    )
    (net (code "60") (name "Net-(U5-VS-)") (class "Default")
      (node (ref "C18") (pin "1") (pinfunction "1_1") (pintype "passive"))
      (node (ref "U5") (pin "6") (pinfunction "VS-_6") (pintype "bidirectional"))
    )
    (net (code "61") (name "PACK_GATE") (class "Default")
      (node (ref "J4") (pin "2") (pinfunction "P$2_2") (pintype "bidirectional"))
      (node (ref "U3") (pin "3.0") (pinfunction "P3.0_3.0") (pintype "bidirectional"))
    )
    (net (code "62") (name "PACK_I_MEAS") (class "Default")
      (node (ref "U3") (pin "5.0") (pinfunction "P5.0_5.0") (pintype "bidirectional"))
      (node (ref "U4") (pin "3") (pinfunction "VOUT_3") (pintype "output"))
    )
    (net (code "63") (name "RS232_RX_PB") (class "Default")
      (node (ref "RS232_PB") (pin "3") (pinfunction "3_3") (pintype "bidirectional"))
      (node (ref "U5") (pin "13") (pinfunction "R1IN_13") (pintype "bidirectional"))
    )
    (net (code "64") (name "RS232_TX_PB") (class "Default")
      (node (ref "RS232_PB") (pin "2") (pinfunction "2_2") (pintype "bidirectional"))
      (node (ref "U5") (pin "14") (pinfunction "T1OUT_14") (pintype "bidirectional"))
    )
    (net (code "65") (name "SER_RX_PB") (class "Default")
      (node (ref "U3") (pin "3.2") (pinfunction "P3.2_3.2") (pintype "bidirectional"))
      (node (ref "U5") (pin "12") (pinfunction "R1OUT_12") (pintype "bidirectional"))
    )
    (net (code "66") (name "SER_TX_IND") (class "Default")
      (node (ref "D10") (pin "C") (pinfunction "C_C") (pintype "passive"))
      (node (ref "J1") (pin "3") (pinfunction "3_3") (pintype "bidirectional"))
      (node (ref "U3") (pin "9.7") (pinfunction "P9.7_9.7") (pintype "bidirectional"))
    )
    (net (code "67") (name "SER_TX_PB") (class "Default")
      (node (ref "U3") (pin "3.3") (pinfunction "P3.3_3.3") (pintype "bidirectional"))
      (node (ref "U5") (pin "11") (pinfunction "T1IN_11") (pintype "bidirectional"))
    )
    (net (code "68") (name "TEMP_1") (class "Default")
      (node (ref "TEMP_1") (pin "2") (pinfunction "2_2") (pintype "bidirectional"))
      (node (ref "U3") (pin "2.5") (pinfunction "P2.5_2.5") (pintype "bidirectional"))
    )
    (net (code "69") (name "V_CHECK_ARRAY") (class "Default")
      (node (ref "R1") (pin "2") (pinfunction "2_2") (pintype "passive"))
      (node (ref "R2") (pin "1") (pinfunction "1_1") (pintype "passive"))
      (node (ref "U3") (pin "5.1") (pinfunction "P5.1_5.1") (pintype "bidirectional"))
    )
    (net (code "70") (name "V_CHECK_OUT") (class "Default")
      (node (ref "R10") (pin "2") (pinfunction "2_2") (pintype "passive"))
      (node (ref "R11") (pin "1") (pinfunction "1_1") (pintype "passive"))
      (node (ref "U3") (pin "5.2") (pinfunction "P5.2_5.2") (pintype "bidirectional"))
    )
    (net (code "71") (name "unconnected-(U$3-NC_1-Pad1)") (class "Default")
      (node (ref "U$3") (pin "1") (pinfunction "NC_1_1") (pintype "bidirectional"))
    )
    (net (code "72") (name "unconnected-(U$3-NC_5-Pad5)") (class "Default")
      (node (ref "U$3") (pin "5") (pinfunction "NC_5_5") (pintype "bidirectional"))
    )
    (net (code "73") (name "unconnected-(U$3-NC_8-Pad8)") (class "Default")
      (node (ref "U$3") (pin "8") (pinfunction "NC_8_8") (pintype "bidirectional"))
    )
    (net (code "74") (name "unconnected-(U1-FAULT-Pad3)") (class "Default")
      (node (ref "U1") (pin "3") (pinfunction "FAULT_3") (pintype "bidirectional"))
    )
    (net (code "75") (name "unconnected-(U1-TIMER-Pad2)") (class "Default")
      (node (ref "U1") (pin "2") (pinfunction "TIMER_2") (pintype "bidirectional"))
    )
    (net (code "76") (name "unconnected-(U3-P1.5-Pad1.5)") (class "Default")
      (node (ref "U3") (pin "1.5") (pinfunction "P1.5_1.5") (pintype "bidirectional"))
    )
    (net (code "77") (name "unconnected-(U3-P2.3-Pad2.3)") (class "Default")
      (node (ref "U3") (pin "2.3") (pinfunction "P2.3_2.3") (pintype "bidirectional"))
    )
    (net (code "78") (name "unconnected-(U3-P2.4-Pad2.4)") (class "Default")
      (node (ref "U3") (pin "2.4") (pinfunction "P2.4_2.4") (pintype "bidirectional"))
    )
    (net (code "79") (name "unconnected-(U3-P2.6-Pad2.6)") (class "Default")
      (node (ref "U3") (pin "2.6") (pinfunction "P2.6_2.6") (pintype "bidirectional"))
    )
    (net (code "80") (name "unconnected-(U3-P2.7-Pad2.7)") (class "Default")
      (node (ref "U3") (pin "2.7") (pinfunction "P2.7_2.7") (pintype "bidirectional"))
    )
    (net (code "81") (name "unconnected-(U3-P4.3-Pad4.3)") (class "Default")
      (node (ref "U3") (pin "4.3") (pinfunction "P4.3_4.3") (pintype "bidirectional"))
    )
    (net (code "82") (name "unconnected-(U3-P4.5-Pad4.5)") (class "Default")
      (node (ref "U3") (pin "4.5") (pinfunction "P4.5_4.5") (pintype "bidirectional"))
    )
    (net (code "83") (name "unconnected-(U3-P4.6-Pad4.6)") (class "Default")
      (node (ref "U3") (pin "4.6") (pinfunction "P4.6_4.6") (pintype "bidirectional"))
    )
    (net (code "84") (name "unconnected-(U3-P4.7-Pad4.7)") (class "Default")
      (node (ref "U3") (pin "4.7") (pinfunction "P4.7_4.7") (pintype "bidirectional"))
    )
    (net (code "85") (name "unconnected-(U3-P5.3-Pad5.3)") (class "Default")
      (node (ref "U3") (pin "5.3") (pinfunction "P5.3_5.3") (pintype "bidirectional"))
    )
    (net (code "86") (name "unconnected-(U3-P5.4-Pad5.4)") (class "Default")
      (node (ref "U3") (pin "5.4") (pinfunction "P5.4_5.4") (pintype "bidirectional"))
    )
    (net (code "87") (name "unconnected-(U3-P5.5-Pad5.5)") (class "Default")
      (node (ref "U3") (pin "5.5") (pinfunction "P5.5_5.5") (pintype "bidirectional"))
    )
    (net (code "88") (name "unconnected-(U3-P5.6-Pad5.6)") (class "Default")
      (node (ref "U3") (pin "5.6") (pinfunction "P5.6_5.6") (pintype "bidirectional"))
    )
    (net (code "89") (name "unconnected-(U3-P6.0-Pad6.0)") (class "Default")
      (node (ref "U3") (pin "6.0") (pinfunction "P6.0_6.0") (pintype "bidirectional"))
    )
    (net (code "90") (name "unconnected-(U3-P6.2-Pad6.2)") (class "Default")
      (node (ref "U3") (pin "6.2") (pinfunction "P6.2_6.2") (pintype "bidirectional"))
    )
    (net (code "91") (name "unconnected-(U3-P6.3-Pad6.3)") (class "Default")
      (node (ref "U3") (pin "6.3") (pinfunction "P6.3_6.3") (pintype "bidirectional"))
    )
    (net (code "92") (name "unconnected-(U3-P6.4-Pad6.4)") (class "Default")
      (node (ref "U3") (pin "6.4") (pinfunction "P6.4_6.4") (pintype "bidirectional"))
    )
    (net (code "93") (name "unconnected-(U3-P6.5-Pad6.5)") (class "Default")
      (node (ref "U3") (pin "6.5") (pinfunction "P6.5_6.5") (pintype "bidirectional"))
    )
    (net (code "94") (name "unconnected-(U3-P6.6-Pad6.6)") (class "Default")
      (node (ref "U3") (pin "6.6") (pinfunction "P6.6_6.6") (pintype "bidirectional"))
    )
    (net (code "95") (name "unconnected-(U3-P6.7-Pad6.7)") (class "Default")
      (node (ref "U3") (pin "6.7") (pinfunction "P6.7_6.7") (pintype "bidirectional"))
    )
    (net (code "96") (name "unconnected-(U3-P7.0-Pad7.0)") (class "Default")
      (node (ref "U3") (pin "7.0") (pinfunction "P7.0_7.0") (pintype "bidirectional"))
    )
    (net (code "97") (name "unconnected-(U3-P7.1-Pad7.1)") (class "Default")
      (node (ref "U3") (pin "7.1") (pinfunction "P7.1_7.1") (pintype "bidirectional"))
    )
    (net (code "98") (name "unconnected-(U3-P7.2-Pad7.2)") (class "Default")
      (node (ref "U3") (pin "7.2") (pinfunction "P7.2_7.2") (pintype "bidirectional"))
    )
    (net (code "99") (name "unconnected-(U3-P7.3-Pad7.3)") (class "Default")
      (node (ref "U3") (pin "7.3") (pinfunction "P7.3_7.3") (pintype "bidirectional"))
    )
    (net (code "100") (name "unconnected-(U3-P7.4-Pad7.4)") (class "Default")
      (node (ref "U3") (pin "7.4") (pinfunction "P7.4_7.4") (pintype "bidirectional"))
    )
    (net (code "101") (name "unconnected-(U3-P7.5-Pad7.5)") (class "Default")
      (node (ref "U3") (pin "7.5") (pinfunction "P7.5_7.5") (pintype "bidirectional"))
    )
    (net (code "102") (name "unconnected-(U3-P7.6-Pad7.6)") (class "Default")
      (node (ref "U3") (pin "7.6") (pinfunction "P7.6_7.6") (pintype "bidirectional"))
    )
    (net (code "103") (name "unconnected-(U3-P7.7-Pad7.7)") (class "Default")
      (node (ref "U3") (pin "7.7") (pinfunction "P7.7_7.7") (pintype "bidirectional"))
    )
    (net (code "104") (name "unconnected-(U3-P8.0-Pad8.0)") (class "Default")
      (node (ref "U3") (pin "8.0") (pinfunction "P8.0_8.0") (pintype "bidirectional"))
    )
    (net (code "105") (name "unconnected-(U3-P8.2-Pad8.2)") (class "Default")
      (node (ref "U3") (pin "8.2") (pinfunction "P8.2_8.2") (pintype "bidirectional"))
    )
    (net (code "106") (name "unconnected-(U3-P8.3-Pad8.3)") (class "Default")
      (node (ref "U3") (pin "8.3") (pinfunction "P8.3_8.3") (pintype "bidirectional"))
    )
    (net (code "107") (name "unconnected-(U3-P8.4-Pad8.4)") (class "Default")
      (node (ref "U3") (pin "8.4") (pinfunction "P8.4_8.4") (pintype "bidirectional"))
    )
    (net (code "108") (name "unconnected-(U3-P8.5-Pad8.5)") (class "Default")
      (node (ref "U3") (pin "8.5") (pinfunction "P8.5_8.5") (pintype "bidirectional"))
    )
    (net (code "109") (name "unconnected-(U3-P8.6-Pad8.6)") (class "Default")
      (node (ref "U3") (pin "8.6") (pinfunction "P8.6_8.6") (pintype "bidirectional"))
    )
    (net (code "110") (name "unconnected-(U3-P8.7-Pad8.7)") (class "Default")
      (node (ref "U3") (pin "8.7") (pinfunction "P8.7_8.7") (pintype "bidirectional"))
    )
    (net (code "111") (name "unconnected-(U3-P9.0-Pad9.0)") (class "Default")
      (node (ref "U3") (pin "9.0") (pinfunction "P9.0_9.0") (pintype "bidirectional"))
    )
    (net (code "112") (name "unconnected-(U3-P9.1-Pad9.1)") (class "Default")
      (node (ref "U3") (pin "9.1") (pinfunction "P9.1_9.1") (pintype "bidirectional"))
    )
    (net (code "113") (name "unconnected-(U3-P9.2-Pad9.2)") (class "Default")
      (node (ref "U3") (pin "9.2") (pinfunction "P9.2_9.2") (pintype "bidirectional"))
    )
    (net (code "114") (name "unconnected-(U3-P9.3-Pad9.3)") (class "Default")
      (node (ref "U3") (pin "9.3") (pinfunction "P9.3_9.3") (pintype "bidirectional"))
    )
    (net (code "115") (name "unconnected-(U3-P9.4-Pad9.4)") (class "Default")
      (node (ref "U3") (pin "9.4") (pinfunction "P9.4_9.4") (pintype "bidirectional"))
    )
    (net (code "116") (name "unconnected-(U3-P9.5-Pad9.5)") (class "Default")
      (node (ref "U3") (pin "9.5") (pinfunction "P9.5_9.5") (pintype "bidirectional"))
    )
    (net (code "117") (name "unconnected-(U3-P9.6-Pad9.6)") (class "Default")
      (node (ref "U3") (pin "9.6") (pinfunction "P9.6_9.6") (pintype "bidirectional"))
    )
    (net (code "118") (name "unconnected-(U3-P10.0-Pad10.0)") (class "Default")
      (node (ref "U3") (pin "10.0") (pinfunction "P10.0_10.0") (pintype "bidirectional"))
    )
    (net (code "119") (name "unconnected-(U3-P10.1-Pad10.1)") (class "Default")
      (node (ref "U3") (pin "10.1") (pinfunction "P10.1_10.1") (pintype "bidirectional"))
    )
    (net (code "120") (name "unconnected-(U3-P10.2-Pad10.2)") (class "Default")
      (node (ref "U3") (pin "10.2") (pinfunction "P10.2_10.2") (pintype "bidirectional"))
    )
    (net (code "121") (name "unconnected-(U3-P10.3-Pad10.3)") (class "Default")
      (node (ref "U3") (pin "10.3") (pinfunction "P10.3_10.3") (pintype "bidirectional"))
    )
    (net (code "122") (name "unconnected-(U3-P10.4-Pad10.4)") (class "Default")
      (node (ref "U3") (pin "10.4") (pinfunction "P10.4_10.4") (pintype "bidirectional"))
    )
    (net (code "123") (name "unconnected-(U3-P10.5-Pad10.5)") (class "Default")
      (node (ref "U3") (pin "10.5") (pinfunction "P10.5_10.5") (pintype "bidirectional"))
    )
    (net (code "124") (name "unconnected-(U3-Pad3V3_1)") (class "Default")
      (node (ref "U3") (pin "3V3_1") (pinfunction "3V3_1_3V3_1") (pintype "bidirectional"))
    )
    (net (code "125") (name "unconnected-(U3-Pad3V3_2)") (class "Default")
      (node (ref "U3") (pin "3V3_2") (pinfunction "3V3_2_3V3_2") (pintype "bidirectional"))
    )
    (net (code "126") (name "unconnected-(U3-Pad3V3_3)") (class "Default")
      (node (ref "U3") (pin "3V3_3") (pinfunction "3V3_3_3V3_3") (pintype "bidirectional"))
    )
    (net (code "127") (name "unconnected-(U3-Pad3V3_4)") (class "Default")
      (node (ref "U3") (pin "3V3_4") (pinfunction "3V3_4_3V3_4") (pintype "bidirectional"))
    )
    (net (code "128") (name "unconnected-(U3-{slash}RST-PadRST)") (class "Default")
      (node (ref "U3") (pin "RST") (pinfunction "/RST_RST") (pintype "bidirectional"))
    )
    (net (code "129") (name "unconnected-(U5-R2IN-Pad8)") (class "Default")
      (node (ref "U5") (pin "8") (pinfunction "R2IN_8") (pintype "bidirectional"))
    )
    (net (code "130") (name "unconnected-(U5-R2OUT-Pad9)") (class "Default")
      (node (ref "U5") (pin "9") (pinfunction "R2OUT_9") (pintype "bidirectional"))
    )
    (net (code "131") (name "unconnected-(U5-T2IN-Pad10)") (class "Default")
      (node (ref "U5") (pin "10") (pinfunction "T2IN_10") (pintype "bidirectional"))
    )
    (net (code "132") (name "unconnected-(U5-T2OUT-Pad7)") (class "Default")
      (node (ref "U5") (pin "7") (pinfunction "T2OUT_7") (pintype "bidirectional"))
    )
  )
)
